# Singularitron_Breathalyzer_Module.net
KiCad netlist of a schematic drawn in EAGLE
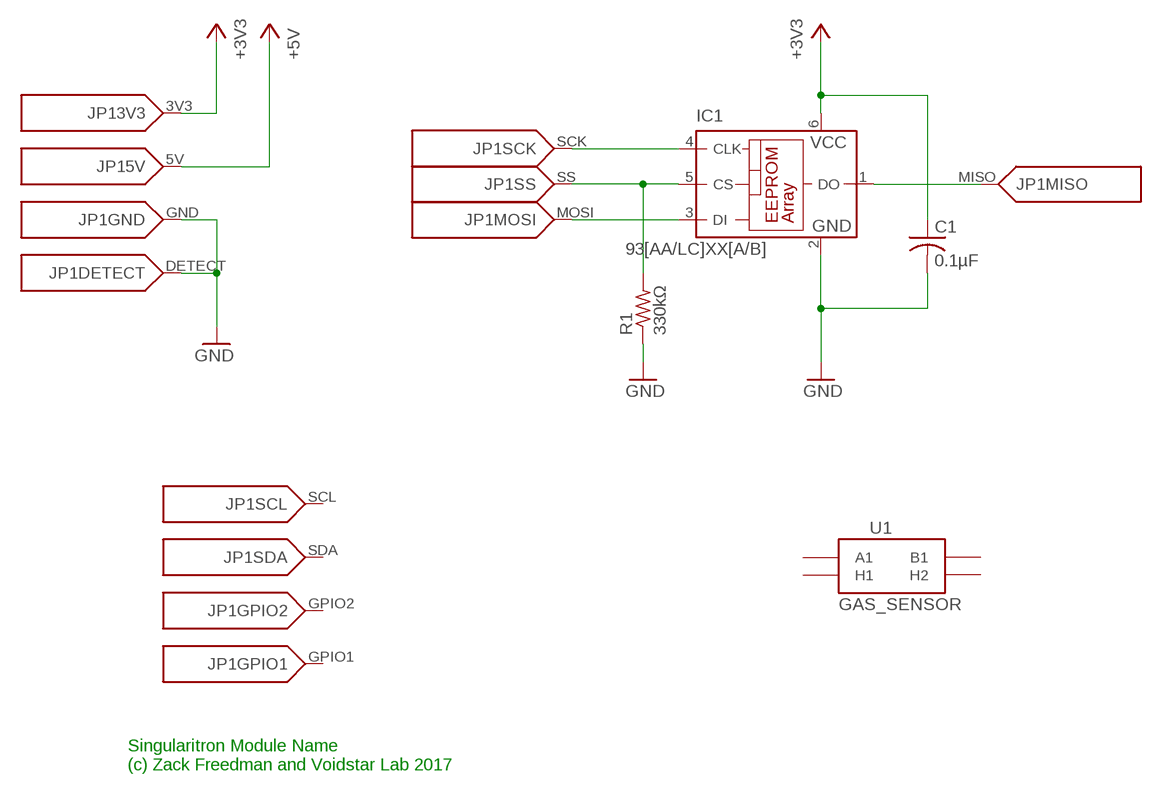
[diagram p0: schematic, sheet 1]

(export (version "E")
  (design (tool "Eeschema 10.0.6"))
  (components
    (comp (ref "C1")
      (value "0.1µF")
      (footprint "eagle-import:C0603")
      (libsource (lib "eagle-import") (part "C-USC0603"))
    )
    (comp (ref "IC1")
      (value "93[AA/LC]XX[A/B]")
      (footprint "eagle-import:SOT23-6")
      (fields (field (name "MPN") "93AA76AT-I/OT"))
      (libsource (lib "eagle-import") (part "9376?AAA"))
    )
    (comp (ref "JP1")
      (value "SINGULARITRON_CART_BASE")
      (footprint "eagle-import:SINGULARITRON_CART_BASE")
      (libsource (lib "eagle-import") (part "SINGULARITRON_CART_BASE"))
    )
    (comp (ref "R1")
      (value "330kΩ")
      (footprint "eagle-import:R0603")
      (libsource (lib "eagle-import") (part "R-US_R0603"))
    )
    (comp (ref "U1")
      (value "GAS_SENSOR")
      (footprint "eagle-import:MQ-3")
      (libsource (lib "eagle-import") (part "GAS_SENSOR"))
    )
  )
  (nets
    (net (code "1") (name "+3V3") (class "Default")
      (node (ref "C1") (pin "1") (pinfunction "1_1") (pintype "passive"))
      (node (ref "IC1") (pin "6") (pinfunction "VCC_6") (pintype "power_in"))
      (node (ref "JP1") (pin "3V3") (pinfunction "P$1_3V3") (pintype "bidirectional"))
    )
    (net (code "2") (name "+5V") (class "Default")
      (node (ref "JP1") (pin "5V") (pinfunction "P$1_5V") (pintype "bidirectional"))
    )
    (net (code "3") (name "GND") (class "Default")
      (node (ref "C1") (pin "2") (pinfunction "2_2") (pintype "passive"))
      (node (ref "IC1") (pin "2") (pinfunction "GND_2") (pintype "power_in"))
      (node (ref "JP1") (pin "DETECT") (pinfunction "P$1_DETECT") (pintype "bidirectional"))
      (node (ref "JP1") (pin "GND") (pinfunction "P$1_GND") (pintype "bidirectional"))
      (node (ref "R1") (pin "1") (pinfunction "1_1") (pintype "passive"))
    )
    (net (code "4") (name "Net-(IC1-CLK)") (class "Default")
      (node (ref "IC1") (pin "4") (pinfunction "CLK_4") (pintype "input"))
      (node (ref "JP1") (pin "SCK") (pinfunction "P$1_SCK") (pintype "bidirectional"))
    )
    (net (code "5") (name "Net-(IC1-CS)") (class "Default")
      (node (ref "IC1") (pin "5") (pinfunction "CS_5") (pintype "input"))
      (node (ref "JP1") (pin "SS") (pinfunction "P$1_SS") (pintype "bidirectional"))
      (node (ref "R1") (pin "2") (pinfunction "2_2") (pintype "passive"))
    )
    (net (code "6") (name "Net-(IC1-DI)") (class "Default")
      (node (ref "IC1") (pin "3") (pinfunction "DI_3") (pintype "input"))
      (node (ref "JP1") (pin "MOSI") (pinfunction "P$1_MOSI") (pintype "bidirectional"))
    )
    (net (code "7") (name "Net-(IC1-DO)") (class "Default")
      (node (ref "IC1") (pin "1") (pinfunction "DO_1") (pintype "tri_state"))
      (node (ref "JP1") (pin "MISO") (pinfunction "P$1_MISO") (pintype "bidirectional"))
    )
    (net (code "8") (name "unconnected-(JP1E-P$1-PadGPIO1)") (class "Default")
      (node (ref "JP1") (pin "GPIO1") (pinfunction "P$1_GPIO1") (pintype "bidirectional"))
    )
    (net (code "9") (name "unconnected-(JP1F-P$1-PadGPIO2)") (class "Default")
      (node (ref "JP1") (pin "GPIO2") (pinfunction "P$1_GPIO2") (pintype "bidirectional"))
    )
    (net (code "10") (name "unconnected-(JP1J-P$1-PadSCL)") (class "Default")
      (node (ref "JP1") (pin "SCL") (pinfunction "P$1_SCL") (pintype "bidirectional"))
    )
    (net (code "11") (name "unconnected-(JP1K-P$1-PadSDA)") (class "Default")
      (node (ref "JP1") (pin "SDA") (pinfunction "P$1_SDA") (pintype "bidirectional"))
    )
    (net (code "12") (name "unconnected-(U1-H1-PadHA)") (class "Default")
      (node (ref "U1") (pin "HA") (pinfunction "H1_HA") (pintype "bidirectional"))
    )
    (net (code "13") (name "unconnected-(U1-H2-PadHB)") (class "Default")
      (node (ref "U1") (pin "HB") (pinfunction "H2_HB") (pintype "bidirectional"))
    )
    (net (code "14") (name "unconnected-(U1-PadA1)") (class "Default")
      (node (ref "U1") (pin "A1") (pinfunction "A1_A1") (pintype "bidirectional"))
    )
    (net (code "15") (name "unconnected-(U1-PadB1)") (class "Default")
      (node (ref "U1") (pin "B1") (pinfunction "B1_B1") (pintype "bidirectional"))
    )
  )
)
